# Power.net
KiCad netlist of a schematic drawn in Altium Designer
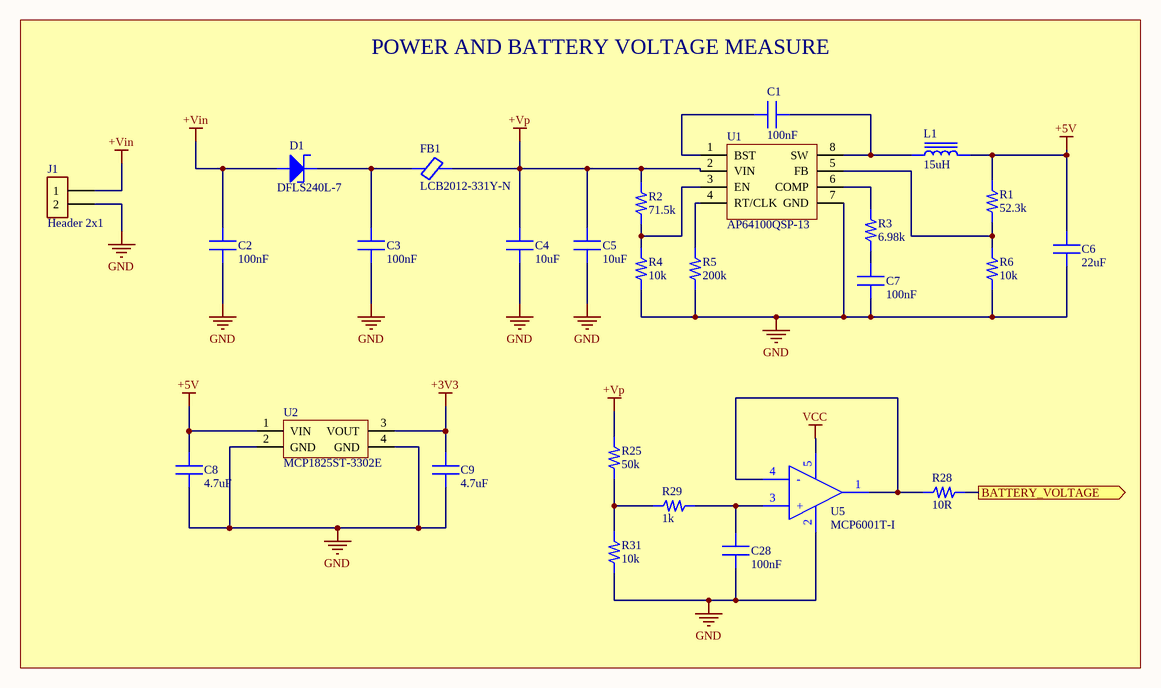
[diagram p0: Power.SchDoc]

(export (version "E")
  (design (tool "Eeschema 10.0.6"))
  (components
    (comp (ref "C1")
      (value "100nF")
      (footprint "CAPC2012X145N 0805")
      (description "MLCC 0805 100nF 50VDC ±10% X7R")
      (fields (field (name "TOLERANCE") "±10 %") (field (name "MANUFACTURER") "SAMSUNG"))
      (libsource (lib "Chicken_Coop_Door_Main_Board") (part "CAP 0805 100nF"))
    )
    (comp (ref "C2")
      (value "100nF")
      (footprint "CAPC2012X145N 0805")
      (description "MLCC 0805 100nF 50VDC ±10% X7R")
      (fields (field (name "TOLERANCE") "±5 %") (field (name "MANUFACTURER") "YAGEO"))
      (libsource (lib "Chicken_Coop_Door_Main_Board_V3") (part "CAP 0805 100nF CC0805JRX7R9BB104"))
    )
    (comp (ref "C3")
      (value "100nF")
      (footprint "CAPC2012X145N 0805")
      (description "MLCC 0805 100nF 50VDC ±10% X7R")
      (fields (field (name "TOLERANCE") "±5 %") (field (name "MANUFACTURER") "YAGEO"))
      (libsource (lib "Chicken_Coop_Door_Main_Board_V3") (part "CAP 0805 100nF CC0805JRX7R9BB104"))
    )
    (comp (ref "C4")
      (value "10uF")
      (footprint "CAPC 1206 3216X180N")
      (description "MLCC (3216) 1206 10uF 50VDC ±10% X5R")
      (fields (field (name "TOLERANCE") "±10%") (field (name "MANUFACTURER") "Samsung Electro-Mechanics"))
      (libsource (lib "Chicken_Coop_Door_Main_Board_V3") (part "CAP 1206 10uF CL31A106KBHNNNE"))
    )
    (comp (ref "C5")
      (value "10uF")
      (footprint "CAPC 1206 3216X180N")
      (description "MLCC (3216) 1206 10uF 50VDC ±10% X5R")
      (fields (field (name "TOLERANCE") "±10%") (field (name "MANUFACTURER") "Samsung Electro-Mechanics"))
      (libsource (lib "Chicken_Coop_Door_Main_Board_V3") (part "CAP 1206 10uF CL31A106KBHNNNE"))
    )
    (comp (ref "C6")
      (value "22uF")
      (footprint "CAPC2012X145N 0805")
      (description "MLCC (2012) 0805 22uF 16VDC ±10% X5R CL21A226KOQNNNE")
      (fields (field (name "TOLERANCE") "±10 %") (field (name "MANUFACTURER") "SAMSUNG"))
      (libsource (lib "Chicken_Coop_Door_Main_Board_V3") (part "CAP 0805 22uF CL21A226KOQNNNE"))
    )
    (comp (ref "C7")
      (value "100nF")
      (footprint "CAPC2012X145N 0805")
      (description "MLCC (2012) 0805 10nF 50VDC ±10% X7R")
      (fields (field (name "TOLERANCE") "±10 %") (field (name "MANUFACTURER") "YAGEO"))
      (libsource (lib "Chicken_Coop_Door_Main_Board_V3") (part "CAP 0805 10nF CC0805KRX7R9BB103"))
    )
    (comp (ref "C8")
      (value "4.7uF")
      (footprint "CAPC2012X145N 0805")
      (description "MLCC (2012) 0805 4.7uF 25VDC ±10% X5R")
      (fields (field (name "TOLERANCE") "±10 %") (field (name "MANUFACTURER") "SAMSUNG"))
      (libsource (lib "Chicken_Coop_Door_Main_Board_V3") (part "CAP 0805 4.7uF CL21A475KAQNNNE"))
    )
    (comp (ref "C9")
      (value "4.7uF")
      (footprint "CAPC2012X145N 0805")
      (description "MLCC (2012) 0805 4.7uF 25VDC ±10% X5R")
      (fields (field (name "TOLERANCE") "±10 %") (field (name "MANUFACTURER") "SAMSUNG"))
      (libsource (lib "Chicken_Coop_Door_Main_Board_V3") (part "CAP 0805 4.7uF CL21A475KAQNNNE"))
    )
    (comp (ref "C28")
      (value "100nF")
      (footprint "CAPC2012X145N 0805")
      (description "MLCC 0805 100nF 50VDC ±10% X7R")
      (fields (field (name "TOLERANCE") "±5 %") (field (name "MANUFACTURER") "YAGEO"))
      (libsource (lib "Chicken_Coop_Door_Main_Board_V3") (part "CAP 0805 100nF CC0805JRX7R9BB104"))
    )
    (comp (ref "D1")
      (value "DFLS240L-7")
      (footprint "DIODE DFLS240L-7  POWERDI 123")
      (description "DIODE SCHOTTK 40V 2A POWERDI 123")
      (fields (field (name "MANUFACTURER") "Diodes Incorporated"))
      (libsource (lib "Chicken_Coop_Door_Main_Board") (part "DIODE SCHOTTKY DFLS240L-7"))
    )
    (comp (ref "FB1")
      (value "LCB2012-331Y-N")
      (footprint "BEADC2012X105N MPZ2012S601ATD25")
      (description "FERRITE BEAD 0805 330R/100MHZ SMD")
      (fields (field (name "MANUFACTURER") "CORE MASTER"))
      (libsource (lib "Chicken_Coop_Door_Main_Board_V3") (part "Ferrite Bead LCB2012-331Y-N"))
    )
    (comp (ref "J1")
      (value "Header 2x1")
      (footprint "JST_B2B-PH-K-S 1x2 Header")
      (description "CON.T.B.2.00MM 2P 180C MALE CONNFLY")
      (fields (field (name "MANUFACTURER") "CONNFLY"))
      (libsource (lib "Chicken_Coop_Door_Main_Board_V3") (part "Header 2x1 DS1066-2MVW6X"))
    )
    (comp (ref "L1")
      (value "15uH")
      (footprint "Inductor SRI1004-150M")
      (description "INDUCTOR POWER 15UH 10X10X4.5MM SMD")
      (fields (field (name "TOLERANCE") "±20 %") (field (name "MANUFACTURER") "CORE MASTER"))
      (libsource (lib "Chicken_Coop_Door_Main_Board_V3") (part "15uH Inductor SRI1004-150M"))
    )
    (comp (ref "R1")
      (value "52.3k")
      (footprint "RES 0805 YAGEO C2012X60N")
      (description "RES.(2012) 0805 52.3K Ohms 1% 1/8W-S 100PPM")
      (fields (field (name "POWER") "1/8W") (field (name "TOLERANCE") "±1 %"))
      (libsource (lib "Chicken_Coop_Door_Main_Board_V3") (part "RES 0805 52.3k 0805S8F5232T5E"))
    )
    (comp (ref "R2")
      (value "71.5k")
      (footprint "RES 0805 YAGEO C2012X60N")
      (description "RES.(2012) 0805 71.5k Ohms 1% 1/8W-S 100PPM")
      (fields (field (name "POWER") "1/8W") (field (name "TOLERANCE") "±1 %"))
      (libsource (lib "Chicken_Coop_Door_Main_Board_V3") (part "RES 0805 71.5k Ohms 0805S8F7152T5E"))
    )
    (comp (ref "R3")
      (value "6.98k")
      (footprint "RES 0805 YAGEO C2012X60N")
      (description "RES.(2012) 0805 6.98K Ohms 1% 1/10W 100PPM")
      (fields (field (name "POWER") "1/8W") (field (name "TOLERANCE") "±1 %"))
      (libsource (lib "Chicken_Coop_Door_Main_Board_V3") (part "RES 0805 6.98k 0805WAF6981T5E"))
    )
    (comp (ref "R4")
      (value "10k")
      (footprint "RES 0805 YAGEO C2012X60N")
      (description "RES.(2012) 0805 10K Ohms 1% 1/8W-S 100PPM")
      (fields (field (name "POWER") "1/8W") (field (name "TOLERANCE") "±1 %"))
      (libsource (lib "Chicken_Coop_Door_Main_Board_V3") (part "RES 0805 10k 0805S8F1002T5E"))
    )
    (comp (ref "R5")
      (value "200k")
      (footprint "RES 0805 YAGEO C2012X60N")
      (description "RES.(2012) 0805 200K Ohms 1% 1/8W-S 100PPM")
      (fields (field (name "POWER") "1/8W") (field (name "TOLERANCE") "±1 %"))
      (libsource (lib "Chicken_Coop_Door_Main_Board_V3") (part "RES 0805 200k 0805S8F2003T5E"))
    )
    (comp (ref "R6")
      (value "10k")
      (footprint "RES 0805 YAGEO C2012X60N")
      (description "RES.(2012) 0805 10K Ohms 1% 1/8W-S 100PPM")
      (fields (field (name "POWER") "1/8W") (field (name "TOLERANCE") "±1 %"))
      (libsource (lib "Chicken_Coop_Door_Main_Board_V3") (part "RES 0805 10k 0805S8F1002T5E"))
    )
    (comp (ref "R25")
      (value "50k")
      (footprint "RES 0805 YAGEO C2012X60N")
      (description "RES.(2012) 0805 50K Ohms 1% 1/8W-S 100PPM")
      (fields (field (name "POWER") "1/8W") (field (name "TOLERANCE") "±1 %"))
      (libsource (lib "Chicken_Coop_Door_Main_Board_V3") (part "RES 0805 50k 0805S8F5002T5E"))
    )
    (comp (ref "R28")
      (value "10R")
      (footprint "RES 0805 YAGEO C2012X60N")
      (description "RES.(2012) 0805 10 Ohms 5% 1/8W-S 400PPM")
      (fields (field (name "POWER") "1/8W") (field (name "TOLERANCE") "±1 %"))
      (libsource (lib "Chicken_Coop_Door_Main_Board_V3") (part "RES 0805 10 Ohms 0805S8J0100T5E"))
    )
    (comp (ref "R29")
      (value "1k")
      (footprint "RES 0805 YAGEO C2012X60N")
      (description "RES.(2012) 0805 1K Ohms 1% 1/8W-S 100PPM")
      (fields (field (name "POWER") "1/8W") (field (name "TOLERANCE") "±1 %"))
      (libsource (lib "Chicken_Coop_Door_Main_Board_V3") (part "RES 0805 1k Ohms 0805S8F1001TDE"))
    )
    (comp (ref "R31")
      (value "10k")
      (footprint "RES 0805 YAGEO C2012X60N")
      (description "RES.(2012) 0805 10K Ohms 1% 1/8W-S 100PPM")
      (fields (field (name "POWER") "1/8W") (field (name "TOLERANCE") "±1 %"))
      (libsource (lib "Chicken_Coop_Door_Main_Board_V3") (part "RES 0805 10k 0805S8F1002T5E"))
    )
    (comp (ref "U1")
      (value "AP64100QSP-13")
      (footprint "AP64100QSP-13 SOIC-8 Buck Converter")
      (fields (field (name "MANUFACTURER") "Diodes Incorporated"))
      (libsource (lib "Chicken_Coop_Door_Main_Board") (part "AP64100QSP-13 Buck converter"))
    )
    (comp (ref "U2")
      (value "MCP1825ST-3302E")
      (footprint "LDO MCP1825ST-3302E/DB  SOT-223_3MC_MCH")
      (description "Linear Voltage Regulator IC Positive Fixed 1 Output 500mA SOT-223-3")
      (fields (field (name "MANUFACTURER") "Microchip Technology"))
      (libsource (lib "Chicken_Coop_Door_Main_Board") (part "LDO 3V3 MCP1825ST-3302E/DB"))
    )
    (comp (ref "U5")
      (value "MCP6001T-I")
      (footprint "MCP6001T-I/OT OPAMP SOT-23-5")
      (description "Standard (General Purpose) Amplifier 1 Circuit Rail-to-Rail SOT-23-5")
      (fields (field (name "MANUFACTURER") "Microchip Technology"))
      (libsource (lib "Chicken_Coop_Door_Main_Board_V3") (part "MCP6001T-I/OT OP-AMP 1 CH LOW POWER"))
    )
  )
  (nets
    (net (code "1") (name "+3V3") (class "Default")
      (node (ref "C9") (pin "2") (pinfunction "2_2") (pintype "passive"))
      (node (ref "U2") (pin "3") (pinfunction "VOUT_3") (pintype "passive"))
    )
    (net (code "2") (name "+5V") (class "Default")
      (node (ref "C6") (pin "2") (pinfunction "2_2") (pintype "passive"))
      (node (ref "C8") (pin "2") (pinfunction "2_2") (pintype "passive"))
      (node (ref "L1") (pin "2") (pinfunction "2_2") (pintype "passive"))
      (node (ref "R1") (pin "2") (pinfunction "2_2") (pintype "passive"))
      (node (ref "U2") (pin "1") (pinfunction "VIN_1") (pintype "passive"))
    )
    (net (code "3") (name "+Vin") (class "Default")
      (node (ref "C2") (pin "2") (pinfunction "2_2") (pintype "passive"))
      (node (ref "D1") (pin "1") (pinfunction "Anode_1") (pintype "passive"))
      (node (ref "J1") (pin "1") (pinfunction "1_1") (pintype "passive"))
    )
    (net (code "4") (name "+Vp") (class "Default")
      (node (ref "C4") (pin "2") (pinfunction "2_2") (pintype "passive"))
      (node (ref "C5") (pin "2") (pinfunction "2_2") (pintype "passive"))
      (node (ref "FB1") (pin "2") (pinfunction "2_2") (pintype "passive"))
      (node (ref "R2") (pin "2") (pinfunction "2_2") (pintype "passive"))
      (node (ref "R25") (pin "2") (pinfunction "2_2") (pintype "passive"))
      (node (ref "U1") (pin "2") (pinfunction "VIN_2") (pintype "passive"))
    )
    (net (code "5") (name "/BATTERY_VOLTAGE") (class "Default")
      (node (ref "R28") (pin "2") (pinfunction "2_2") (pintype "passive"))
    )
    (net (code "6") (name "GND") (class "Default")
      (node (ref "C2") (pin "1") (pinfunction "1_1") (pintype "passive"))
      (node (ref "C28") (pin "1") (pinfunction "1_1") (pintype "passive"))
      (node (ref "C3") (pin "1") (pinfunction "1_1") (pintype "passive"))
      (node (ref "C4") (pin "1") (pinfunction "1_1") (pintype "passive"))
      (node (ref "C5") (pin "1") (pinfunction "1_1") (pintype "passive"))
      (node (ref "C6") (pin "1") (pinfunction "1_1") (pintype "passive"))
      (node (ref "C7") (pin "1") (pinfunction "1_1") (pintype "passive"))
      (node (ref "C8") (pin "1") (pinfunction "1_1") (pintype "passive"))
      (node (ref "C9") (pin "1") (pinfunction "1_1") (pintype "passive"))
      (node (ref "J1") (pin "2") (pinfunction "2_2") (pintype "passive"))
      (node (ref "R31") (pin "1") (pinfunction "1_1") (pintype "passive"))
      (node (ref "R4") (pin "1") (pinfunction "1_1") (pintype "passive"))
      (node (ref "R5") (pin "1") (pinfunction "1_1") (pintype "passive"))
      (node (ref "R6") (pin "1") (pinfunction "1_1") (pintype "passive"))
      (node (ref "U1") (pin "7") (pinfunction "GND_7") (pintype "passive"))
      (node (ref "U2") (pin "2") (pinfunction "GND_2") (pintype "passive"))
      (node (ref "U2") (pin "4") (pinfunction "GND_4") (pintype "passive"))
      (node (ref "U5") (pin "2") (pinfunction "VSS_2") (pintype "passive"))
    )
    (net (code "7") (name "Net-(C7-Pad2)") (class "Default")
      (node (ref "C7") (pin "2") (pinfunction "2_2") (pintype "passive"))
      (node (ref "R3") (pin "1") (pinfunction "1_1") (pintype "passive"))
    )
    (net (code "8") (name "Net-(D1-Cathode)") (class "Default")
      (node (ref "C3") (pin "2") (pinfunction "2_2") (pintype "passive"))
      (node (ref "D1") (pin "2") (pinfunction "Cathode_2") (pintype "passive"))
      (node (ref "FB1") (pin "1") (pinfunction "1_1") (pintype "passive"))
    )
    (net (code "9") (name "Net-(R25-Pad1)") (class "Default")
      (node (ref "R25") (pin "1") (pinfunction "1_1") (pintype "passive"))
      (node (ref "R29") (pin "1") (pinfunction "1_1") (pintype "passive"))
      (node (ref "R31") (pin "2") (pinfunction "2_2") (pintype "passive"))
    )
    (net (code "10") (name "Net-(U1-BST)") (class "Default")
      (node (ref "C1") (pin "1") (pinfunction "1_1") (pintype "passive"))
      (node (ref "U1") (pin "1") (pinfunction "BST_1") (pintype "passive"))
    )
    (net (code "11") (name "Net-(U1-COMP)") (class "Default")
      (node (ref "R3") (pin "2") (pinfunction "2_2") (pintype "passive"))
      (node (ref "U1") (pin "6") (pinfunction "COMP_6") (pintype "passive"))
    )
    (net (code "12") (name "Net-(U1-EN)") (class "Default")
      (node (ref "R2") (pin "1") (pinfunction "1_1") (pintype "passive"))
      (node (ref "R4") (pin "2") (pinfunction "2_2") (pintype "passive"))
      (node (ref "U1") (pin "3") (pinfunction "EN_3") (pintype "passive"))
    )
    (net (code "13") (name "Net-(U1-FB)") (class "Default")
      (node (ref "R1") (pin "1") (pinfunction "1_1") (pintype "passive"))
      (node (ref "R6") (pin "2") (pinfunction "2_2") (pintype "passive"))
      (node (ref "U1") (pin "5") (pinfunction "FB_5") (pintype "passive"))
    )
    (net (code "14") (name "Net-(U1-RT{slash}CLK)") (class "Default")
      (node (ref "R5") (pin "2") (pinfunction "2_2") (pintype "passive"))
      (node (ref "U1") (pin "4") (pinfunction "RT/CLK_4") (pintype "passive"))
    )
    (net (code "15") (name "Net-(U1-SW)") (class "Default")
      (node (ref "C1") (pin "2") (pinfunction "2_2") (pintype "passive"))
      (node (ref "L1") (pin "1") (pinfunction "1_1") (pintype "passive"))
      (node (ref "U1") (pin "8") (pinfunction "SW_8") (pintype "passive"))
    )
    (net (code "16") (name "Net-(U5-+)") (class "Default")
      (node (ref "C28") (pin "2") (pinfunction "2_2") (pintype "passive"))
      (node (ref "R29") (pin "2") (pinfunction "2_2") (pintype "passive"))
      (node (ref "U5") (pin "3") (pinfunction "+_3") (pintype "passive"))
    )
    (net (code "17") (name "Net-(U5--)") (class "Default")
      (node (ref "R28") (pin "1") (pinfunction "1_1") (pintype "passive"))
      (node (ref "U5") (pin "1") (pinfunction "Vout_1") (pintype "passive"))
      (node (ref "U5") (pin "4") (pinfunction "-_4") (pintype "passive"))
    )
    (net (code "18") (name "VCC") (class "Default")
      (node (ref "U5") (pin "5") (pinfunction "VDD_5") (pintype "passive"))
    )
  )
)
